# 03_LemonAutopilot_3.net
KiCad netlist of a schematic drawn in Altium Designer
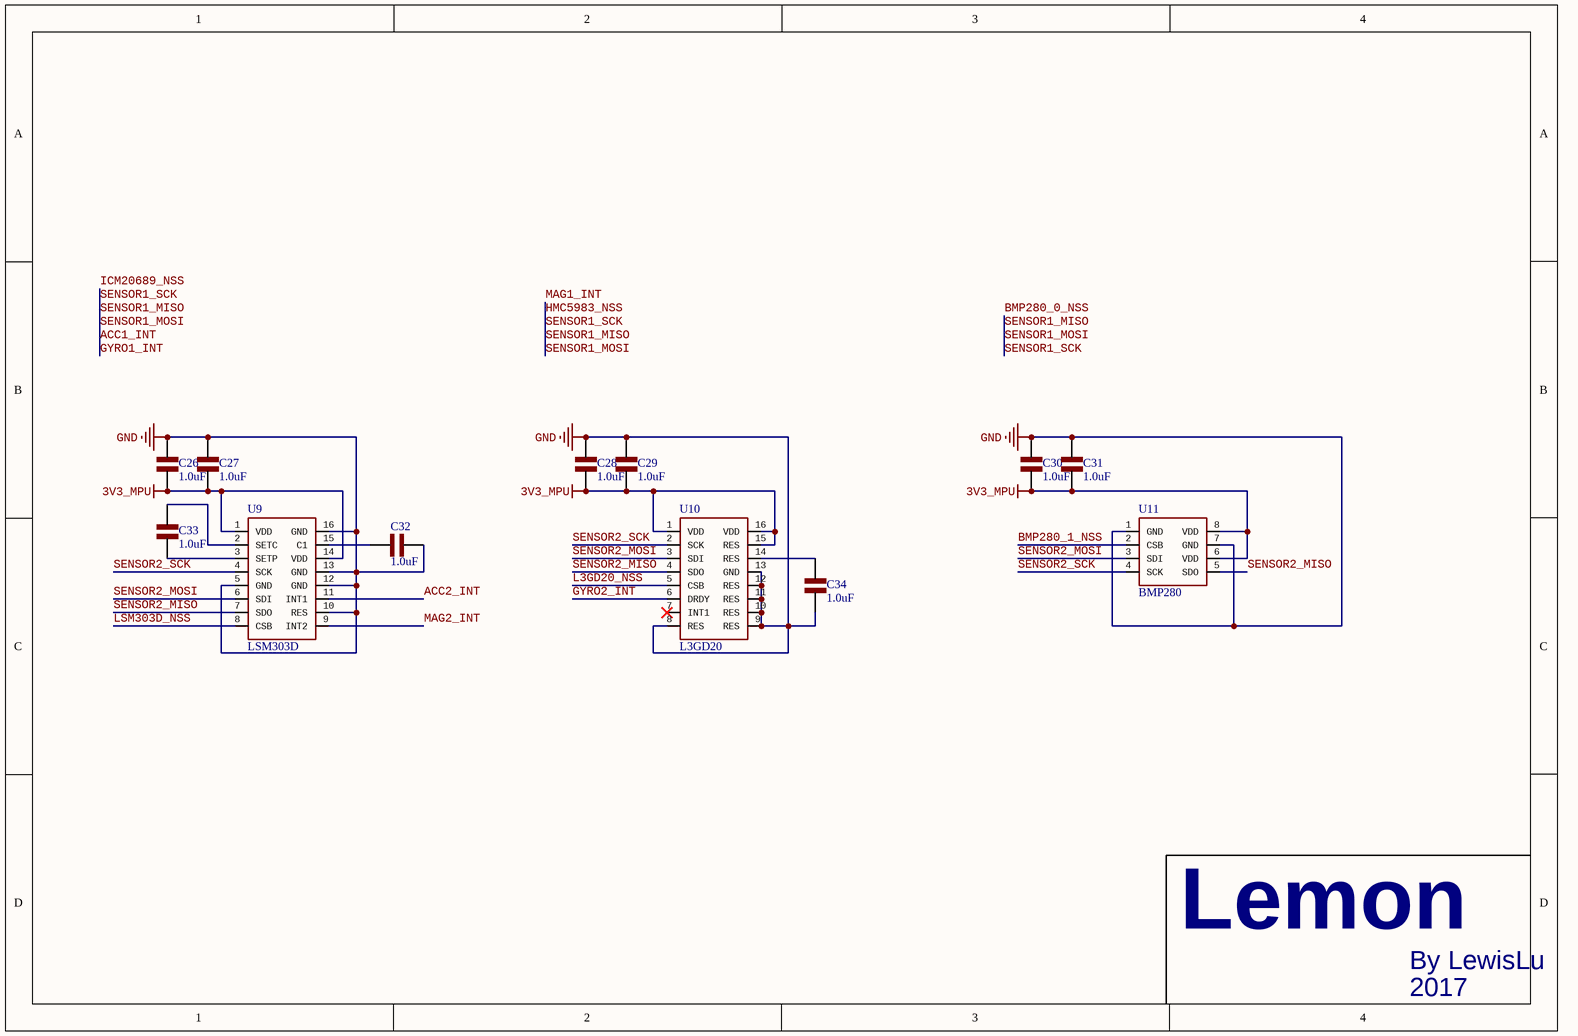
[diagram p0: 03.LemonAutopilot_3.SchDoc]

(export (version "E")
  (design (tool "Eeschema 10.0.6"))
  (components
    (comp (ref "C26") (value "1.0uF") (footprint "0603_C") (libsource (lib "Library") (part "C0603")))
    (comp (ref "C27") (value "1.0uF") (footprint "0603_C") (libsource (lib "Library") (part "C0603")))
    (comp (ref "C28") (value "1.0uF") (footprint "0603_C") (libsource (lib "Library") (part "C0603")))
    (comp (ref "C29") (value "1.0uF") (footprint "0603_C") (libsource (lib "Library") (part "C0603")))
    (comp (ref "C30") (value "1.0uF") (footprint "0603_C") (libsource (lib "") (part "C0603_1")))
    (comp (ref "C31") (value "1.0uF") (footprint "0603_C") (libsource (lib "") (part "C0603_1")))
    (comp (ref "C32") (value "1.0uF") (footprint "0603_C") (libsource (lib "") (part "C0603_2")))
    (comp (ref "C33") (value "1.0uF") (footprint "0603_C") (libsource (lib "Library") (part "C0603")))
    (comp (ref "C34") (value "1.0uF") (footprint "0603_C") (libsource (lib "Library") (part "C0603")))
    (comp (ref "U9") (value "LSM303D") (libsource (lib "Library") (part "LSM303D")))
    (comp (ref "U10") (value "L3GD20") (libsource (lib "Library") (part "L3GD20")))
    (comp (ref "U11") (value "BMP280") (libsource (lib "Library") (part "BMP280")))
  )
  (nets
    (net (code "2") (name "/ACC2_INT") (class "Default")
      (node (ref "U9") (pin "11") (pinfunction "INT1_11") (pintype "passive"))
    )
    (net (code "3") (name "/BMP280_1_NSS") (class "Default")
      (node (ref "U11") (pin "2") (pinfunction "CSB_2") (pintype "passive"))
    )
    (net (code "4") (name "/GYRO2_INT") (class "Default")
      (node (ref "U10") (pin "6") (pinfunction "DRDY_6") (pintype "passive"))
    )
    (net (code "5") (name "/L3GD20_NSS") (class "Default")
      (node (ref "U10") (pin "5") (pinfunction "CSB_5") (pintype "passive"))
    )
    (net (code "6") (name "/LSM303D_NSS") (class "Default")
      (node (ref "U9") (pin "8") (pinfunction "CSB_8") (pintype "passive"))
    )
    (net (code "7") (name "/MAG2_INT") (class "Default")
      (node (ref "U9") (pin "9") (pinfunction "INT2_9") (pintype "passive"))
    )
    (net (code "8") (name "/SENSOR2_MISO") (class "Default")
      (node (ref "U10") (pin "4") (pinfunction "SDO_4") (pintype "passive"))
      (node (ref "U11") (pin "5") (pinfunction "SDO_5") (pintype "passive"))
      (node (ref "U9") (pin "7") (pinfunction "SDO_7") (pintype "passive"))
    )
    (net (code "9") (name "/SENSOR2_MOSI") (class "Default")
      (node (ref "U10") (pin "3") (pinfunction "SDI_3") (pintype "passive"))
      (node (ref "U11") (pin "3") (pinfunction "SDI_3") (pintype "passive"))
      (node (ref "U9") (pin "6") (pinfunction "SDI_6") (pintype "passive"))
    )
    (net (code "10") (name "/SENSOR2_SCK") (class "Default")
      (node (ref "U10") (pin "2") (pinfunction "SCK_2") (pintype "passive"))
      (node (ref "U11") (pin "4") (pinfunction "SCK_4") (pintype "passive"))
      (node (ref "U9") (pin "4") (pinfunction "SCK_4") (pintype "passive"))
    )
    (net (code "11") (name "3V3_MPU") (class "Default")
      (node (ref "C26") (pin "1") (pinfunction "1_1") (pintype "passive"))
      (node (ref "C27") (pin "1") (pinfunction "1_1") (pintype "passive"))
      (node (ref "C28") (pin "1") (pinfunction "1_1") (pintype "passive"))
      (node (ref "C29") (pin "1") (pinfunction "1_1") (pintype "passive"))
      (node (ref "C30") (pin "2") (pinfunction "2_2") (pintype "passive"))
      (node (ref "C31") (pin "2") (pinfunction "2_2") (pintype "passive"))
      (node (ref "U10") (pin "1") (pinfunction "VDD_1") (pintype "passive"))
      (node (ref "U10") (pin "15") (pinfunction "RES_15") (pintype "passive"))
      (node (ref "U10") (pin "16") (pinfunction "VDD_16") (pintype "passive"))
      (node (ref "U11") (pin "6") (pinfunction "VDD_6") (pintype "passive"))
      (node (ref "U11") (pin "8") (pinfunction "VDD_8") (pintype "passive"))
      (node (ref "U9") (pin "1") (pinfunction "VDD_1") (pintype "passive"))
      (node (ref "U9") (pin "14") (pinfunction "VDD_14") (pintype "passive"))
    )
    (net (code "12") (name "GND") (class "Default")
      (node (ref "C26") (pin "2") (pinfunction "2_2") (pintype "passive"))
      (node (ref "C27") (pin "2") (pinfunction "2_2") (pintype "passive"))
      (node (ref "C28") (pin "2") (pinfunction "2_2") (pintype "passive"))
      (node (ref "C29") (pin "2") (pinfunction "2_2") (pintype "passive"))
      (node (ref "C30") (pin "1") (pinfunction "1_1") (pintype "passive"))
      (node (ref "C31") (pin "1") (pinfunction "1_1") (pintype "passive"))
      (node (ref "C32") (pin "1") (pinfunction "1_1") (pintype "passive"))
      (node (ref "C34") (pin "1") (pinfunction "1_1") (pintype "passive"))
      (node (ref "U10") (pin "10") (pinfunction "RES_10") (pintype "passive"))
      (node (ref "U10") (pin "11") (pinfunction "RES_11") (pintype "passive"))
      (node (ref "U10") (pin "12") (pinfunction "RES_12") (pintype "passive"))
      (node (ref "U10") (pin "13") (pinfunction "GND_13") (pintype "passive"))
      (node (ref "U10") (pin "8") (pinfunction "RES_8") (pintype "passive"))
      (node (ref "U10") (pin "9") (pinfunction "RES_9") (pintype "passive"))
      (node (ref "U11") (pin "1") (pinfunction "GND_1") (pintype "passive"))
      (node (ref "U11") (pin "7") (pinfunction "GND_7") (pintype "passive"))
      (node (ref "U9") (pin "10") (pinfunction "RES_10") (pintype "passive"))
      (node (ref "U9") (pin "12") (pinfunction "GND_12") (pintype "passive"))
      (node (ref "U9") (pin "13") (pinfunction "GND_13") (pintype "passive"))
      (node (ref "U9") (pin "16") (pinfunction "GND_16") (pintype "passive"))
      (node (ref "U9") (pin "5") (pinfunction "GND_5") (pintype "passive"))
    )
    (net (code "13") (name "Net-(C34-Pad2)") (class "Default")
      (node (ref "C34") (pin "2") (pinfunction "2_2") (pintype "passive"))
      (node (ref "U10") (pin "14") (pinfunction "RES_14") (pintype "passive"))
    )
    (net (code "14") (name "Net-(U9-C1)") (class "Default")
      (node (ref "C32") (pin "2") (pinfunction "2_2") (pintype "passive"))
      (node (ref "U9") (pin "15") (pinfunction "C1_15") (pintype "passive"))
    )
    (net (code "15") (name "Net-(U9-SETC)") (class "Default")
      (node (ref "C33") (pin "2") (pinfunction "2_2") (pintype "passive"))
      (node (ref "U9") (pin "2") (pinfunction "SETC_2") (pintype "passive"))
    )
    (net (code "16") (name "Net-(U9-SETP)") (class "Default")
      (node (ref "C33") (pin "1") (pinfunction "1_1") (pintype "passive"))
      (node (ref "U9") (pin "3") (pinfunction "SETP_3") (pintype "passive"))
    )
    (net (code "17") (name "unconnected-(U10-INT1-Pad7)") (class "Default")
      (node (ref "U10") (pin "7") (pinfunction "INT1_7") (pintype "passive+no_connect"))
    )
  )
)
